# B201X.net
KiCad netlist of a schematic drawn in EAGLE
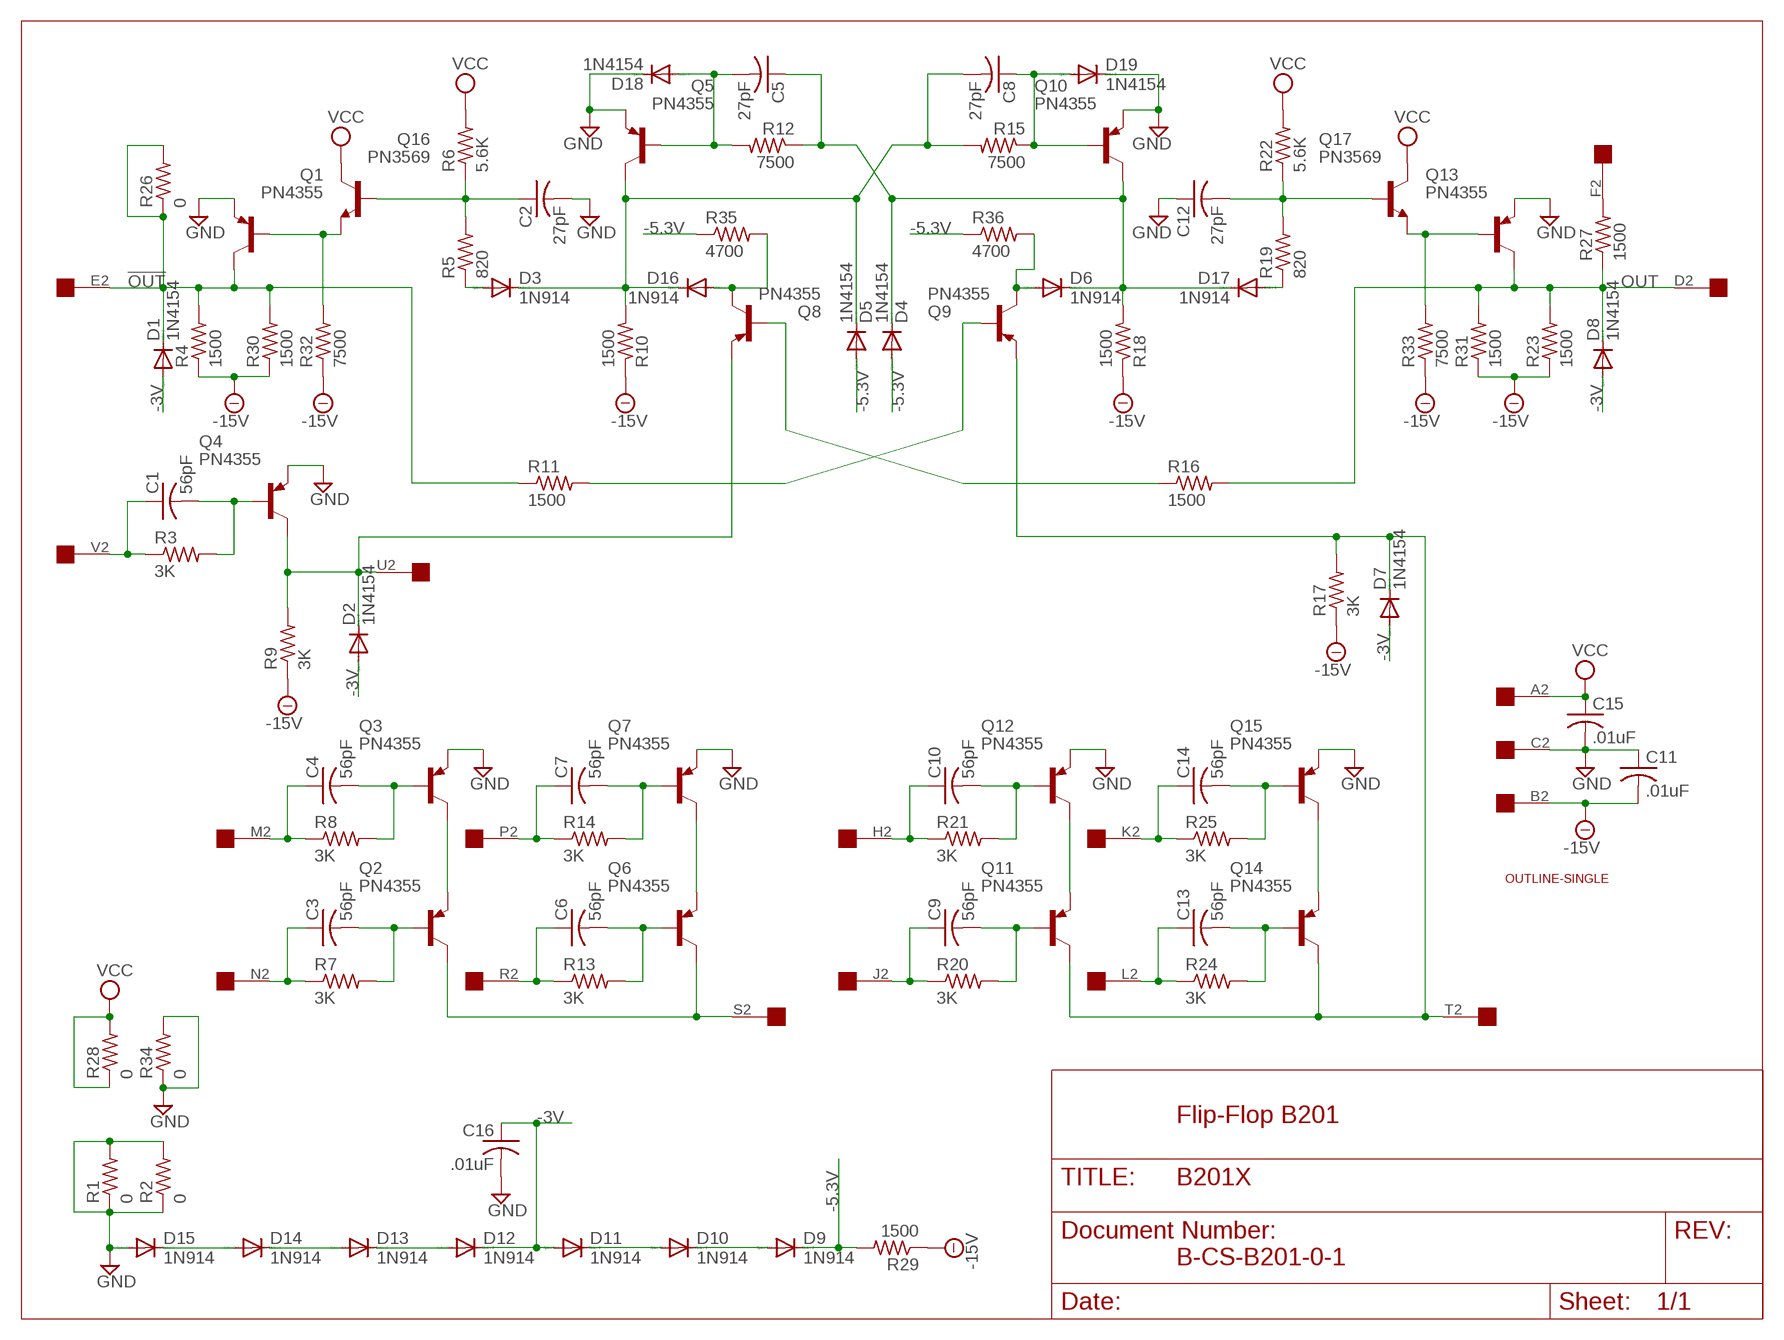
[diagram p0: schematic, sheet 1]

(export (version "E")
  (design (tool "Eeschema 10.0.6"))
  (components
    (comp (ref "C1")
      (value "56pF")
      (footprint "eagle-import:C063-025X075")
      (libsource (lib "eagle-import") (part "C-US"))
    )
    (comp (ref "C2")
      (value "27pF")
      (footprint "eagle-import:C063-025X075")
      (libsource (lib "eagle-import") (part "C-US"))
    )
    (comp (ref "C3")
      (value "56pF")
      (footprint "eagle-import:C063-025X075")
      (libsource (lib "eagle-import") (part "C-US"))
    )
    (comp (ref "C4")
      (value "56pF")
      (footprint "eagle-import:C063-025X075")
      (libsource (lib "eagle-import") (part "C-US"))
    )
    (comp (ref "C5")
      (value "27pF")
      (footprint "eagle-import:C063-025X075")
      (libsource (lib "eagle-import") (part "C-US"))
    )
    (comp (ref "C6")
      (value "56pF")
      (footprint "eagle-import:C063-025X075")
      (libsource (lib "eagle-import") (part "C-US"))
    )
    (comp (ref "C7")
      (value "56pF")
      (footprint "eagle-import:C063-025X075")
      (libsource (lib "eagle-import") (part "C-US"))
    )
    (comp (ref "C8")
      (value "27pF")
      (footprint "eagle-import:C063-025X075")
      (libsource (lib "eagle-import") (part "C-US"))
    )
    (comp (ref "C9")
      (value "56pF")
      (footprint "eagle-import:C063-025X075")
      (libsource (lib "eagle-import") (part "C-US"))
    )
    (comp (ref "C10")
      (value "56pF")
      (footprint "eagle-import:C063-025X075")
      (libsource (lib "eagle-import") (part "C-US"))
    )
    (comp (ref "C11")
      (value ".01uF")
      (footprint "eagle-import:C063-025X075")
      (libsource (lib "eagle-import") (part "C-US"))
    )
    (comp (ref "C12")
      (value "27pF")
      (footprint "eagle-import:C063-025X075")
      (libsource (lib "eagle-import") (part "C-US"))
    )
    (comp (ref "C13")
      (value "56pF")
      (footprint "eagle-import:C063-025X075")
      (libsource (lib "eagle-import") (part "C-US"))
    )
    (comp (ref "C14")
      (value "56pF")
      (footprint "eagle-import:C063-025X075")
      (libsource (lib "eagle-import") (part "C-US"))
    )
    (comp (ref "C15")
      (value ".01uF")
      (footprint "eagle-import:C063-025X075")
      (libsource (lib "eagle-import") (part "C-US"))
    )
    (comp (ref "C16")
      (value ".01uF")
      (footprint "eagle-import:C063-025X075")
      (libsource (lib "eagle-import") (part "C-US"))
    )
    (comp (ref "D1")
      (value "1N4154")
      (footprint "eagle-import:DO35-10")
      (libsource (lib "eagle-import") (part "DIODE-DO35-10"))
    )
    (comp (ref "D2")
      (value "1N4154")
      (footprint "eagle-import:DO35-10")
      (libsource (lib "eagle-import") (part "DIODE-DO35-10"))
    )
    (comp (ref "D3")
      (value "1N914")
      (footprint "eagle-import:DO35-10")
      (libsource (lib "eagle-import") (part "DIODE-DO35-10"))
    )
    (comp (ref "D4")
      (value "1N4154")
      (footprint "eagle-import:DO35-10")
      (libsource (lib "eagle-import") (part "DIODE-DO35-10"))
    )
    (comp (ref "D5")
      (value "1N4154")
      (footprint "eagle-import:DO35-10")
      (libsource (lib "eagle-import") (part "DIODE-DO35-10"))
    )
    (comp (ref "D6")
      (value "1N914")
      (footprint "eagle-import:DO35-10")
      (libsource (lib "eagle-import") (part "DIODE-DO35-10"))
    )
    (comp (ref "D7")
      (value "1N4154")
      (footprint "eagle-import:DO35-10")
      (libsource (lib "eagle-import") (part "DIODE-DO35-10"))
    )
    (comp (ref "D8")
      (value "1N4154")
      (footprint "eagle-import:DO35-10")
      (libsource (lib "eagle-import") (part "DIODE-DO35-10"))
    )
    (comp (ref "D9")
      (value "1N914")
      (footprint "eagle-import:DO35-10")
      (libsource (lib "eagle-import") (part "DIODE-DO35-10"))
    )
    (comp (ref "D10")
      (value "1N914")
      (footprint "eagle-import:DO35-10")
      (libsource (lib "eagle-import") (part "DIODE-DO35-10"))
    )
    (comp (ref "D11")
      (value "1N914")
      (footprint "eagle-import:DO35-10")
      (libsource (lib "eagle-import") (part "DIODE-DO35-10"))
    )
    (comp (ref "D12")
      (value "1N914")
      (footprint "eagle-import:DO35-10")
      (libsource (lib "eagle-import") (part "DIODE-DO35-10"))
    )
    (comp (ref "D13")
      (value "1N914")
      (footprint "eagle-import:DO35-10")
      (libsource (lib "eagle-import") (part "DIODE-DO35-10"))
    )
    (comp (ref "D14")
      (value "1N914")
      (footprint "eagle-import:DO35-10")
      (libsource (lib "eagle-import") (part "DIODE-DO35-10"))
    )
    (comp (ref "D15")
      (value "1N914")
      (footprint "eagle-import:DO35-10")
      (libsource (lib "eagle-import") (part "DIODE-DO35-10"))
    )
    (comp (ref "D16")
      (value "1N914")
      (footprint "eagle-import:DO35-10")
      (libsource (lib "eagle-import") (part "DIODE-DO35-10"))
    )
    (comp (ref "D17")
      (value "1N914")
      (footprint "eagle-import:DO35-10")
      (libsource (lib "eagle-import") (part "DIODE-DO35-10"))
    )
    (comp (ref "D18")
      (value "1N4154")
      (footprint "eagle-import:DO35-10")
      (libsource (lib "eagle-import") (part "DIODE-DO35-10"))
    )
    (comp (ref "D19")
      (value "1N4154")
      (footprint "eagle-import:DO35-10")
      (libsource (lib "eagle-import") (part "DIODE-DO35-10"))
    )
    (comp (ref "Q1")
      (value "PN4355")
      (footprint "eagle-import:TO5")
      (libsource (lib "eagle-import") (part "-PNP-TO5"))
    )
    (comp (ref "Q2")
      (value "PN4355")
      (footprint "eagle-import:TO5")
      (libsource (lib "eagle-import") (part "-PNP-TO5"))
    )
    (comp (ref "Q3")
      (value "PN4355")
      (footprint "eagle-import:TO5")
      (libsource (lib "eagle-import") (part "-PNP-TO5"))
    )
    (comp (ref "Q4")
      (value "PN4355")
      (footprint "eagle-import:TO5")
      (libsource (lib "eagle-import") (part "-PNP-TO5"))
    )
    (comp (ref "Q5")
      (value "PN4355")
      (footprint "eagle-import:TO5")
      (libsource (lib "eagle-import") (part "-PNP-TO5"))
    )
    (comp (ref "Q6")
      (value "PN4355")
      (footprint "eagle-import:TO5")
      (libsource (lib "eagle-import") (part "-PNP-TO5"))
    )
    (comp (ref "Q7")
      (value "PN4355")
      (footprint "eagle-import:TO5")
      (libsource (lib "eagle-import") (part "-PNP-TO5"))
    )
    (comp (ref "Q8")
      (value "PN4355")
      (footprint "eagle-import:TO5")
      (libsource (lib "eagle-import") (part "-PNP-TO5"))
    )
    (comp (ref "Q9")
      (value "PN4355")
      (footprint "eagle-import:TO5")
      (libsource (lib "eagle-import") (part "-PNP-TO5"))
    )
    (comp (ref "Q10")
      (value "PN4355")
      (footprint "eagle-import:TO5")
      (libsource (lib "eagle-import") (part "-PNP-TO5"))
    )
    (comp (ref "Q11")
      (value "PN4355")
      (footprint "eagle-import:TO5")
      (libsource (lib "eagle-import") (part "-PNP-TO5"))
    )
    (comp (ref "Q12")
      (value "PN4355")
      (footprint "eagle-import:TO5")
      (libsource (lib "eagle-import") (part "-PNP-TO5"))
    )
    (comp (ref "Q13")
      (value "PN4355")
      (footprint "eagle-import:TO5")
      (libsource (lib "eagle-import") (part "-PNP-TO5"))
    )
    (comp (ref "Q14")
      (value "PN4355")
      (footprint "eagle-import:TO5")
      (libsource (lib "eagle-import") (part "-PNP-TO5"))
    )
    (comp (ref "Q15")
      (value "PN4355")
      (footprint "eagle-import:TO5")
      (libsource (lib "eagle-import") (part "-PNP-TO5"))
    )
    (comp (ref "Q16")
      (value "PN3569")
      (footprint "eagle-import:TO5")
      (libsource (lib "eagle-import") (part "-NPN-TO5"))
    )
    (comp (ref "Q17")
      (value "PN3569")
      (footprint "eagle-import:TO5")
      (libsource (lib "eagle-import") (part "-NPN-TO5"))
    )
    (comp (ref "R1")
      (value "0")
      (footprint "eagle-import:0207_10")
      (libsource (lib "eagle-import") (part "R-US_0207/10"))
    )
    (comp (ref "R2")
      (value "0")
      (footprint "eagle-import:0207_10")
      (libsource (lib "eagle-import") (part "R-US_0207/10"))
    )
    (comp (ref "R3")
      (value "3K")
      (footprint "eagle-import:0207_10")
      (libsource (lib "eagle-import") (part "R-US_0207/10"))
    )
    (comp (ref "R4")
      (value "1500")
      (footprint "eagle-import:0207_10")
      (libsource (lib "eagle-import") (part "R-US_0207/10"))
    )
    (comp (ref "R5")
      (value "820")
      (footprint "eagle-import:0207_10")
      (libsource (lib "eagle-import") (part "R-US_0207/10"))
    )
    (comp (ref "R6")
      (value "5.6K")
      (footprint "eagle-import:0207_10")
      (libsource (lib "eagle-import") (part "R-US_0207/10"))
    )
    (comp (ref "R7")
      (value "3K")
      (footprint "eagle-import:0207_10")
      (libsource (lib "eagle-import") (part "R-US_0207/10"))
    )
    (comp (ref "R8")
      (value "3K")
      (footprint "eagle-import:0207_10")
      (libsource (lib "eagle-import") (part "R-US_0207/10"))
    )
    (comp (ref "R9")
      (value "3K")
      (footprint "eagle-import:0207_10")
      (libsource (lib "eagle-import") (part "R-US_0207/10"))
    )
    (comp (ref "R10")
      (value "1500")
      (footprint "eagle-import:0207_10")
      (libsource (lib "eagle-import") (part "R-US_0207/10"))
    )
    (comp (ref "R11")
      (value "1500")
      (footprint "eagle-import:0207_10")
      (libsource (lib "eagle-import") (part "R-US_0207/10"))
    )
    (comp (ref "R12")
      (value "7500")
      (footprint "eagle-import:0207_10")
      (libsource (lib "eagle-import") (part "R-US_0207/10"))
    )
    (comp (ref "R13")
      (value "3K")
      (footprint "eagle-import:0207_10")
      (libsource (lib "eagle-import") (part "R-US_0207/10"))
    )
    (comp (ref "R14")
      (value "3K")
      (footprint "eagle-import:0207_10")
      (libsource (lib "eagle-import") (part "R-US_0207/10"))
    )
    (comp (ref "R15")
      (value "7500")
      (footprint "eagle-import:0207_10")
      (libsource (lib "eagle-import") (part "R-US_0207/10"))
    )
    (comp (ref "R16")
      (value "1500")
      (footprint "eagle-import:0207_10")
      (libsource (lib "eagle-import") (part "R-US_0207/10"))
    )
    (comp (ref "R17")
      (value "3K")
      (footprint "eagle-import:0207_10")
      (libsource (lib "eagle-import") (part "R-US_0207/10"))
    )
    (comp (ref "R18")
      (value "1500")
      (footprint "eagle-import:0207_10")
      (libsource (lib "eagle-import") (part "R-US_0207/10"))
    )
    (comp (ref "R19")
      (value "820")
      (footprint "eagle-import:0207_10")
      (libsource (lib "eagle-import") (part "R-US_0207/10"))
    )
    (comp (ref "R20")
      (value "3K")
      (footprint "eagle-import:0207_10")
      (libsource (lib "eagle-import") (part "R-US_0207/10"))
    )
    (comp (ref "R21")
      (value "3K")
      (footprint "eagle-import:0207_10")
      (libsource (lib "eagle-import") (part "R-US_0207/10"))
    )
    (comp (ref "R22")
      (value "5.6K")
      (footprint "eagle-import:0207_10")
      (libsource (lib "eagle-import") (part "R-US_0207/10"))
    )
    (comp (ref "R23")
      (value "1500")
      (footprint "eagle-import:0207_10")
      (libsource (lib "eagle-import") (part "R-US_0207/10"))
    )
    (comp (ref "R24")
      (value "3K")
      (footprint "eagle-import:0207_10")
      (libsource (lib "eagle-import") (part "R-US_0207/10"))
    )
    (comp (ref "R25")
      (value "3K")
      (footprint "eagle-import:0207_10")
      (libsource (lib "eagle-import") (part "R-US_0207/10"))
    )
    (comp (ref "R26")
      (value "0")
      (footprint "eagle-import:0207_10")
      (libsource (lib "eagle-import") (part "R-US_0207/10"))
    )
    (comp (ref "R27")
      (value "1500")
      (footprint "eagle-import:0207_10")
      (libsource (lib "eagle-import") (part "R-US_0207/10"))
    )
    (comp (ref "R28")
      (value "0")
      (footprint "eagle-import:0207_10")
      (libsource (lib "eagle-import") (part "R-US_0207/10"))
    )
    (comp (ref "R29")
      (value "1500")
      (footprint "eagle-import:0207_10")
      (libsource (lib "eagle-import") (part "R-US_0207/10"))
    )
    (comp (ref "R30")
      (value "1500")
      (footprint "eagle-import:0207_10")
      (libsource (lib "eagle-import") (part "R-US_0207/10"))
    )
    (comp (ref "R31")
      (value "1500")
      (footprint "eagle-import:0207_10")
      (libsource (lib "eagle-import") (part "R-US_0207/10"))
    )
    (comp (ref "R32")
      (value "7500")
      (footprint "eagle-import:0207_10")
      (libsource (lib "eagle-import") (part "R-US_0207/10"))
    )
    (comp (ref "R33")
      (value "7500")
      (footprint "eagle-import:0207_10")
      (libsource (lib "eagle-import") (part "R-US_0207/10"))
    )
    (comp (ref "R34")
      (value "0")
      (footprint "eagle-import:0207_10")
      (libsource (lib "eagle-import") (part "R-US_0207/10"))
    )
    (comp (ref "R35")
      (value "4700")
      (footprint "eagle-import:0207_10")
      (libsource (lib "eagle-import") (part "R-US_0207/10"))
    )
    (comp (ref "R36")
      (value "4700")
      (footprint "eagle-import:0207_10")
      (libsource (lib "eagle-import") (part "R-US_0207/10"))
    )
    (comp (ref "U$1")
      (value "OUTLINE-SINGLE")
      (footprint "eagle-import:SINGLE")
      (libsource (lib "eagle-import") (part "OUTLINE-SINGLE"))
    )
    (comp (ref "U$2")
      (value "EDGE-1")
      (footprint "eagle-import:EDGE-CON1")
      (libsource (lib "eagle-import") (part "EDGE-1"))
    )
  )
  (nets
    (net (code "1") (name "-15V") (class "Default")
      (node (ref "C11") (pin "2") (pinfunction "2_2") (pintype "passive"))
      (node (ref "R10") (pin "1") (pinfunction "1_1") (pintype "passive"))
      (node (ref "R17") (pin "1") (pinfunction "1_1") (pintype "passive"))
      (node (ref "R18") (pin "1") (pinfunction "1_1") (pintype "passive"))
      (node (ref "R23") (pin "1") (pinfunction "1_1") (pintype "passive"))
      (node (ref "R29") (pin "1") (pinfunction "1_1") (pintype "passive"))
      (node (ref "R30") (pin "1") (pinfunction "1_1") (pintype "passive"))
      (node (ref "R31") (pin "1") (pinfunction "1_1") (pintype "passive"))
      (node (ref "R32") (pin "1") (pinfunction "1_1") (pintype "passive"))
      (node (ref "R33") (pin "1") (pinfunction "1_1") (pintype "passive"))
      (node (ref "R4") (pin "1") (pinfunction "1_1") (pintype "passive"))
      (node (ref "R9") (pin "1") (pinfunction "1_1") (pintype "passive"))
      (node (ref "U$2") (pin "B2") (pinfunction "1_B2") (pintype "bidirectional"))
    )
    (net (code "2") (name "/-3V") (class "Default")
      (node (ref "C16") (pin "1") (pinfunction "1_1") (pintype "passive"))
      (node (ref "D1") (pin "A") (pinfunction "A_A") (pintype "passive"))
      (node (ref "D11") (pin "A") (pinfunction "A_A") (pintype "passive"))
      (node (ref "D12") (pin "C") (pinfunction "C_C") (pintype "passive"))
      (node (ref "D2") (pin "A") (pinfunction "A_A") (pintype "passive"))
      (node (ref "D7") (pin "A") (pinfunction "A_A") (pintype "passive"))
      (node (ref "D8") (pin "A") (pinfunction "A_A") (pintype "passive"))
    )
    (net (code "3") (name "/-5.3V") (class "Default")
      (node (ref "D4") (pin "A") (pinfunction "A_A") (pintype "passive"))
      (node (ref "D5") (pin "A") (pinfunction "A_A") (pintype "passive"))
      (node (ref "D9") (pin "C") (pinfunction "C_C") (pintype "passive"))
      (node (ref "R29") (pin "2") (pinfunction "2_2") (pintype "passive"))
      (node (ref "R35") (pin "1") (pinfunction "1_1") (pintype "passive"))
      (node (ref "R36") (pin "1") (pinfunction "1_1") (pintype "passive"))
    )
    (net (code "4") (name "/OUT") (class "Default")
      (node (ref "D8") (pin "C") (pinfunction "C_C") (pintype "passive"))
      (node (ref "Q13") (pin "3") (pinfunction "C_3") (pintype "passive"))
      (node (ref "R16") (pin "2") (pinfunction "2_2") (pintype "passive"))
      (node (ref "R23") (pin "2") (pinfunction "2_2") (pintype "passive"))
      (node (ref "R27") (pin "1") (pinfunction "1_1") (pintype "passive"))
      (node (ref "R31") (pin "2") (pinfunction "2_2") (pintype "passive"))
      (node (ref "U$2") (pin "D2") (pinfunction "1_D2") (pintype "bidirectional"))
    )
    (net (code "5") (name "/~{OUT}") (class "Default")
      (node (ref "D1") (pin "C") (pinfunction "C_C") (pintype "passive"))
      (node (ref "Q1") (pin "3") (pinfunction "C_3") (pintype "passive"))
      (node (ref "R11") (pin "1") (pinfunction "1_1") (pintype "passive"))
      (node (ref "R26") (pin "1") (pinfunction "1_1") (pintype "passive"))
      (node (ref "R26") (pin "2") (pinfunction "2_2") (pintype "passive"))
      (node (ref "R30") (pin "2") (pinfunction "2_2") (pintype "passive"))
      (node (ref "R4") (pin "2") (pinfunction "2_2") (pintype "passive"))
      (node (ref "U$2") (pin "E2") (pinfunction "1_E2") (pintype "bidirectional"))
    )
    (net (code "6") (name "GND") (class "Default")
      (node (ref "C11") (pin "1") (pinfunction "1_1") (pintype "passive"))
      (node (ref "C12") (pin "1") (pinfunction "1_1") (pintype "passive"))
      (node (ref "C15") (pin "2") (pinfunction "2_2") (pintype "passive"))
      (node (ref "C16") (pin "2") (pinfunction "2_2") (pintype "passive"))
      (node (ref "C2") (pin "2") (pinfunction "2_2") (pintype "passive"))
      (node (ref "D15") (pin "A") (pinfunction "A_A") (pintype "passive"))
      (node (ref "D18") (pin "C") (pinfunction "C_C") (pintype "passive"))
      (node (ref "D19") (pin "C") (pinfunction "C_C") (pintype "passive"))
      (node (ref "Q1") (pin "1") (pinfunction "E_1") (pintype "passive"))
      (node (ref "Q10") (pin "1") (pinfunction "E_1") (pintype "passive"))
      (node (ref "Q12") (pin "1") (pinfunction "E_1") (pintype "passive"))
      (node (ref "Q13") (pin "1") (pinfunction "E_1") (pintype "passive"))
      (node (ref "Q15") (pin "1") (pinfunction "E_1") (pintype "passive"))
      (node (ref "Q3") (pin "1") (pinfunction "E_1") (pintype "passive"))
      (node (ref "Q4") (pin "1") (pinfunction "E_1") (pintype "passive"))
      (node (ref "Q5") (pin "1") (pinfunction "E_1") (pintype "passive"))
      (node (ref "Q7") (pin "1") (pinfunction "E_1") (pintype "passive"))
      (node (ref "R1") (pin "1") (pinfunction "1_1") (pintype "passive"))
      (node (ref "R1") (pin "2") (pinfunction "2_2") (pintype "passive"))
      (node (ref "R2") (pin "1") (pinfunction "1_1") (pintype "passive"))
      (node (ref "R2") (pin "2") (pinfunction "2_2") (pintype "passive"))
      (node (ref "R34") (pin "1") (pinfunction "1_1") (pintype "passive"))
      (node (ref "R34") (pin "2") (pinfunction "2_2") (pintype "passive"))
      (node (ref "U$2") (pin "C2") (pinfunction "1_C2") (pintype "bidirectional"))
    )
    (net (code "7") (name "Net-(D3-PadA)") (class "Default")
      (node (ref "D3") (pin "A") (pinfunction "A_A") (pintype "passive"))
      (node (ref "R5") (pin "1") (pinfunction "1_1") (pintype "passive"))
    )
    (net (code "8") (name "Net-(D10-PadA)") (class "Default")
      (node (ref "D10") (pin "A") (pinfunction "A_A") (pintype "passive"))
      (node (ref "D11") (pin "C") (pinfunction "C_C") (pintype "passive"))
    )
    (net (code "9") (name "Net-(D10-PadC)") (class "Default")
      (node (ref "D10") (pin "C") (pinfunction "C_C") (pintype "passive"))
      (node (ref "D9") (pin "A") (pinfunction "A_A") (pintype "passive"))
    )
    (net (code "10") (name "Net-(D12-PadA)") (class "Default")
      (node (ref "D12") (pin "A") (pinfunction "A_A") (pintype "passive"))
      (node (ref "D13") (pin "C") (pinfunction "C_C") (pintype "passive"))
    )
    (net (code "11") (name "Net-(D13-PadA)") (class "Default")
      (node (ref "D13") (pin "A") (pinfunction "A_A") (pintype "passive"))
      (node (ref "D14") (pin "C") (pinfunction "C_C") (pintype "passive"))
    )
    (net (code "12") (name "Net-(D14-PadA)") (class "Default")
      (node (ref "D14") (pin "A") (pinfunction "A_A") (pintype "passive"))
      (node (ref "D15") (pin "C") (pinfunction "C_C") (pintype "passive"))
    )
    (net (code "13") (name "Net-(D17-PadA)") (class "Default")
      (node (ref "D17") (pin "A") (pinfunction "A_A") (pintype "passive"))
      (node (ref "R19") (pin "1") (pinfunction "1_1") (pintype "passive"))
    )
    (net (code "14") (name "Net-(Q1-B)") (class "Default")
      (node (ref "Q1") (pin "2") (pinfunction "B_2") (pintype "passive"))
      (node (ref "Q16") (pin "1") (pinfunction "E_1") (pintype "passive"))
      (node (ref "R32") (pin "2") (pinfunction "2_2") (pintype "passive"))
    )
    (net (code "15") (name "Net-(Q2-B)") (class "Default")
      (node (ref "C3") (pin "2") (pinfunction "2_2") (pintype "passive"))
      (node (ref "Q2") (pin "2") (pinfunction "B_2") (pintype "passive"))
      (node (ref "R7") (pin "2") (pinfunction "2_2") (pintype "passive"))
    )
    (net (code "16") (name "Net-(Q2-C)") (class "Default")
      (node (ref "Q2") (pin "3") (pinfunction "C_3") (pintype "passive"))
      (node (ref "Q6") (pin "3") (pinfunction "C_3") (pintype "passive"))
      (node (ref "U$2") (pin "S2") (pinfunction "1_S2") (pintype "bidirectional"))
    )
    (net (code "17") (name "Net-(Q2-E)") (class "Default")
      (node (ref "Q2") (pin "1") (pinfunction "E_1") (pintype "passive"))
      (node (ref "Q3") (pin "3") (pinfunction "C_3") (pintype "passive"))
    )
    (net (code "18") (name "Net-(Q3-B)") (class "Default")
      (node (ref "C4") (pin "2") (pinfunction "2_2") (pintype "passive"))
      (node (ref "Q3") (pin "2") (pinfunction "B_2") (pintype "passive"))
      (node (ref "R8") (pin "2") (pinfunction "2_2") (pintype "passive"))
    )
    (net (code "19") (name "Net-(Q4-B)") (class "Default")
      (node (ref "C1") (pin "2") (pinfunction "2_2") (pintype "passive"))
      (node (ref "Q4") (pin "2") (pinfunction "B_2") (pintype "passive"))
      (node (ref "R3") (pin "2") (pinfunction "2_2") (pintype "passive"))
    )
    (net (code "20") (name "Net-(Q4-C)") (class "Default")
      (node (ref "D2") (pin "C") (pinfunction "C_C") (pintype "passive"))
      (node (ref "Q4") (pin "3") (pinfunction "C_3") (pintype "passive"))
      (node (ref "Q8") (pin "1") (pinfunction "E_1") (pintype "passive"))
      (node (ref "R9") (pin "2") (pinfunction "2_2") (pintype "passive"))
      (node (ref "U$2") (pin "U2") (pinfunction "1_U2") (pintype "bidirectional"))
    )
    (net (code "21") (name "Net-(Q5-B)") (class "Default")
      (node (ref "C5") (pin "2") (pinfunction "2_2") (pintype "passive"))
      (node (ref "D18") (pin "A") (pinfunction "A_A") (pintype "passive"))
      (node (ref "Q5") (pin "2") (pinfunction "B_2") (pintype "passive"))
      (node (ref "R12") (pin "2") (pinfunction "2_2") (pintype "passive"))
    )
    (net (code "22") (name "Net-(Q5-C)") (class "Default")
      (node (ref "C8") (pin "2") (pinfunction "2_2") (pintype "passive"))
      (node (ref "D16") (pin "C") (pinfunction "C_C") (pintype "passive"))
      (node (ref "D3") (pin "C") (pinfunction "C_C") (pintype "passive"))
      (node (ref "D5") (pin "C") (pinfunction "C_C") (pintype "passive"))
      (node (ref "Q5") (pin "3") (pinfunction "C_3") (pintype "passive"))
      (node (ref "R10") (pin "2") (pinfunction "2_2") (pintype "passive"))
      (node (ref "R15") (pin "2") (pinfunction "2_2") (pintype "passive"))
    )
    (net (code "23") (name "Net-(Q6-B)") (class "Default")
      (node (ref "C6") (pin "2") (pinfunction "2_2") (pintype "passive"))
      (node (ref "Q6") (pin "2") (pinfunction "B_2") (pintype "passive"))
      (node (ref "R13") (pin "2") (pinfunction "2_2") (pintype "passive"))
    )
    (net (code "24") (name "Net-(Q6-E)") (class "Default")
      (node (ref "Q6") (pin "1") (pinfunction "E_1") (pintype "passive"))
      (node (ref "Q7") (pin "3") (pinfunction "C_3") (pintype "passive"))
    )
    (net (code "25") (name "Net-(Q7-B)") (class "Default")
      (node (ref "C7") (pin "2") (pinfunction "2_2") (pintype "passive"))
      (node (ref "Q7") (pin "2") (pinfunction "B_2") (pintype "passive"))
      (node (ref "R14") (pin "2") (pinfunction "2_2") (pintype "passive"))
    )
    (net (code "26") (name "Net-(Q8-B)") (class "Default")
      (node (ref "Q8") (pin "2") (pinfunction "B_2") (pintype "passive"))
      (node (ref "R16") (pin "1") (pinfunction "1_1") (pintype "passive"))
    )
    (net (code "27") (name "Net-(Q8-C)") (class "Default")
      (node (ref "D16") (pin "A") (pinfunction "A_A") (pintype "passive"))
      (node (ref "Q8") (pin "3") (pinfunction "C_3") (pintype "passive"))
      (node (ref "R35") (pin "2") (pinfunction "2_2") (pintype "passive"))
    )
    (net (code "28") (name "Net-(Q9-B)") (class "Default")
      (node (ref "Q9") (pin "2") (pinfunction "B_2") (pintype "passive"))
      (node (ref "R11") (pin "2") (pinfunction "2_2") (pintype "passive"))
    )
    (net (code "29") (name "Net-(Q9-C)") (class "Default")
      (node (ref "D6") (pin "A") (pinfunction "A_A") (pintype "passive"))
      (node (ref "Q9") (pin "3") (pinfunction "C_3") (pintype "passive"))
      (node (ref "R36") (pin "2") (pinfunction "2_2") (pintype "passive"))
    )
    (net (code "30") (name "Net-(Q10-B)") (class "Default")
      (node (ref "C8") (pin "1") (pinfunction "1_1") (pintype "passive"))
      (node (ref "D19") (pin "A") (pinfunction "A_A") (pintype "passive"))
      (node (ref "Q10") (pin "2") (pinfunction "B_2") (pintype "passive"))
      (node (ref "R15") (pin "1") (pinfunction "1_1") (pintype "passive"))
    )
    (net (code "31") (name "Net-(Q10-C)") (class "Default")
      (node (ref "C5") (pin "1") (pinfunction "1_1") (pintype "passive"))
      (node (ref "D17") (pin "C") (pinfunction "C_C") (pintype "passive"))
      (node (ref "D4") (pin "C") (pinfunction "C_C") (pintype "passive"))
      (node (ref "D6") (pin "C") (pinfunction "C_C") (pintype "passive"))
      (node (ref "Q10") (pin "3") (pinfunction "C_3") (pintype "passive"))
      (node (ref "R12") (pin "1") (pinfunction "1_1") (pintype "passive"))
      (node (ref "R18") (pin "2") (pinfunction "2_2") (pintype "passive"))
    )
    (net (code "32") (name "Net-(Q11-B)") (class "Default")
      (node (ref "C9") (pin "2") (pinfunction "2_2") (pintype "passive"))
      (node (ref "Q11") (pin "2") (pinfunction "B_2") (pintype "passive"))
      (node (ref "R20") (pin "2") (pinfunction "2_2") (pintype "passive"))
    )
    (net (code "33") (name "Net-(Q11-C)") (class "Default")
      (node (ref "D7") (pin "C") (pinfunction "C_C") (pintype "passive"))
      (node (ref "Q11") (pin "3") (pinfunction "C_3") (pintype "passive"))
      (node (ref "Q14") (pin "3") (pinfunction "C_3") (pintype "passive"))
      (node (ref "Q9") (pin "1") (pinfunction "E_1") (pintype "passive"))
      (node (ref "R17") (pin "2") (pinfunction "2_2") (pintype "passive"))
      (node (ref "U$2") (pin "T2") (pinfunction "1_T2") (pintype "bidirectional"))
    )
    (net (code "34") (name "Net-(Q11-E)") (class "Default")
      (node (ref "Q11") (pin "1") (pinfunction "E_1") (pintype "passive"))
      (node (ref "Q12") (pin "3") (pinfunction "C_3") (pintype "passive"))
    )
    (net (code "35") (name "Net-(Q12-B)") (class "Default")
      (node (ref "C10") (pin "2") (pinfunction "2_2") (pintype "passive"))
      (node (ref "Q12") (pin "2") (pinfunction "B_2") (pintype "passive"))
      (node (ref "R21") (pin "2") (pinfunction "2_2") (pintype "passive"))
    )
    (net (code "36") (name "Net-(Q13-B)") (class "Default")
      (node (ref "Q13") (pin "2") (pinfunction "B_2") (pintype "passive"))
      (node (ref "Q17") (pin "1") (pinfunction "E_1") (pintype "passive"))
      (node (ref "R33") (pin "2") (pinfunction "2_2") (pintype "passive"))
    )
    (net (code "37") (name "Net-(Q14-B)") (class "Default")
      (node (ref "C13") (pin "2") (pinfunction "2_2") (pintype "passive"))
      (node (ref "Q14") (pin "2") (pinfunction "B_2") (pintype "passive"))
      (node (ref "R24") (pin "2") (pinfunction "2_2") (pintype "passive"))
    )
    (net (code "38") (name "Net-(Q14-E)") (class "Default")
      (node (ref "Q14") (pin "1") (pinfunction "E_1") (pintype "passive"))
      (node (ref "Q15") (pin "3") (pinfunction "C_3") (pintype "passive"))
    )
    (net (code "39") (name "Net-(Q15-B)") (class "Default")
      (node (ref "C14") (pin "2") (pinfunction "2_2") (pintype "passive"))
      (node (ref "Q15") (pin "2") (pinfunction "B_2") (pintype "passive"))
      (node (ref "R25") (pin "2") (pinfunction "2_2") (pintype "passive"))
    )
    (net (code "40") (name "Net-(Q16-B)") (class "Default")
      (node (ref "C2") (pin "1") (pinfunction "1_1") (pintype "passive"))
      (node (ref "Q16") (pin "2") (pinfunction "B_2") (pintype "passive"))
      (node (ref "R5") (pin "2") (pinfunction "2_2") (pintype "passive"))
      (node (ref "R6") (pin "1") (pinfunction "1_1") (pintype "passive"))
    )
    (net (code "41") (name "Net-(Q17-B)") (class "Default")
      (node (ref "C12") (pin "2") (pinfunction "2_2") (pintype "passive"))
      (node (ref "Q17") (pin "2") (pinfunction "B_2") (pintype "passive"))
      (node (ref "R19") (pin "2") (pinfunction "2_2") (pintype "passive"))
      (node (ref "R22") (pin "1") (pinfunction "1_1") (pintype "passive"))
    )
    (net (code "42") (name "Net-(U$2F-1)") (class "Default")
      (node (ref "R27") (pin "2") (pinfunction "2_2") (pintype "passive"))
      (node (ref "U$2") (pin "F2") (pinfunction "1_F2") (pintype "bidirectional"))
    )
    (net (code "43") (name "Net-(U$2G-1)") (class "Default")
      (node (ref "C10") (pin "1") (pinfunction "1_1") (pintype "passive"))
      (node (ref "R21") (pin "1") (pinfunction "1_1") (pintype "passive"))
      (node (ref "U$2") (pin "H2") (pinfunction "1_H2") (pintype "bidirectional"))
    )
    (net (code "44") (name "Net-(U$2H-1)") (class "Default")
      (node (ref "C9") (pin "1") (pinfunction "1_1") (pintype "passive"))
      (node (ref "R20") (pin "1") (pinfunction "1_1") (pintype "passive"))
      (node (ref "U$2") (pin "J2") (pinfunction "1_J2") (pintype "bidirectional"))
    )
    (net (code "45") (name "Net-(U$2I-1)") (class "Default")
      (node (ref "C14") (pin "1") (pinfunction "1_1") (pintype "passive"))
      (node (ref "R25") (pin "1") (pinfunction "1_1") (pintype "passive"))
      (node (ref "U$2") (pin "K2") (pinfunction "1_K2") (pintype "bidirectional"))
    )
    (net (code "46") (name "Net-(U$2J-1)") (class "Default")
      (node (ref "C13") (pin "1") (pinfunction "1_1") (pintype "passive"))
      (node (ref "R24") (pin "1") (pinfunction "1_1") (pintype "passive"))
      (node (ref "U$2") (pin "L2") (pinfunction "1_L2") (pintype "bidirectional"))
    )
    (net (code "47") (name "Net-(U$2K-1)") (class "Default")
      (node (ref "C4") (pin "1") (pinfunction "1_1") (pintype "passive"))
      (node (ref "R8") (pin "1") (pinfunction "1_1") (pintype "passive"))
      (node (ref "U$2") (pin "M2") (pinfunction "1_M2") (pintype "bidirectional"))
    )
    (net (code "48") (name "Net-(U$2L-1)") (class "Default")
      (node (ref "C3") (pin "1") (pinfunction "1_1") (pintype "passive"))
      (node (ref "R7") (pin "1") (pinfunction "1_1") (pintype "passive"))
      (node (ref "U$2") (pin "N2") (pinfunction "1_N2") (pintype "bidirectional"))
    )
    (net (code "49") (name "Net-(U$2M-1)") (class "Default")
      (node (ref "C7") (pin "1") (pinfunction "1_1") (pintype "passive"))
      (node (ref "R14") (pin "1") (pinfunction "1_1") (pintype "passive"))
      (node (ref "U$2") (pin "P2") (pinfunction "1_P2") (pintype "bidirectional"))
    )
    (net (code "50") (name "Net-(U$2N-1)") (class "Default")
      (node (ref "C6") (pin "1") (pinfunction "1_1") (pintype "passive"))
      (node (ref "R13") (pin "1") (pinfunction "1_1") (pintype "passive"))
      (node (ref "U$2") (pin "R2") (pinfunction "1_R2") (pintype "bidirectional"))
    )
    (net (code "51") (name "Net-(U$2R-1)") (class "Default")
      (node (ref "C1") (pin "1") (pinfunction "1_1") (pintype "passive"))
      (node (ref "R3") (pin "1") (pinfunction "1_1") (pintype "passive"))
      (node (ref "U$2") (pin "V2") (pinfunction "1_V2") (pintype "bidirectional"))
    )
    (net (code "52") (name "VCC") (class "Default")
      (node (ref "C15") (pin "1") (pinfunction "1_1") (pintype "passive"))
      (node (ref "Q16") (pin "3") (pinfunction "C_3") (pintype "passive"))
      (node (ref "Q17") (pin "3") (pinfunction "C_3") (pintype "passive"))
      (node (ref "R22") (pin "2") (pinfunction "2_2") (pintype "passive"))
      (node (ref "R28") (pin "1") (pinfunction "1_1") (pintype "passive"))
      (node (ref "R28") (pin "2") (pinfunction "2_2") (pintype "passive"))
      (node (ref "R6") (pin "2") (pinfunction "2_2") (pintype "passive"))
      (node (ref "U$2") (pin "A2") (pinfunction "1_A2") (pintype "bidirectional"))
    )
  )
)
